# interface_dac_sma_feedback.net
KiCad netlist of a schematic drawn in EAGLE
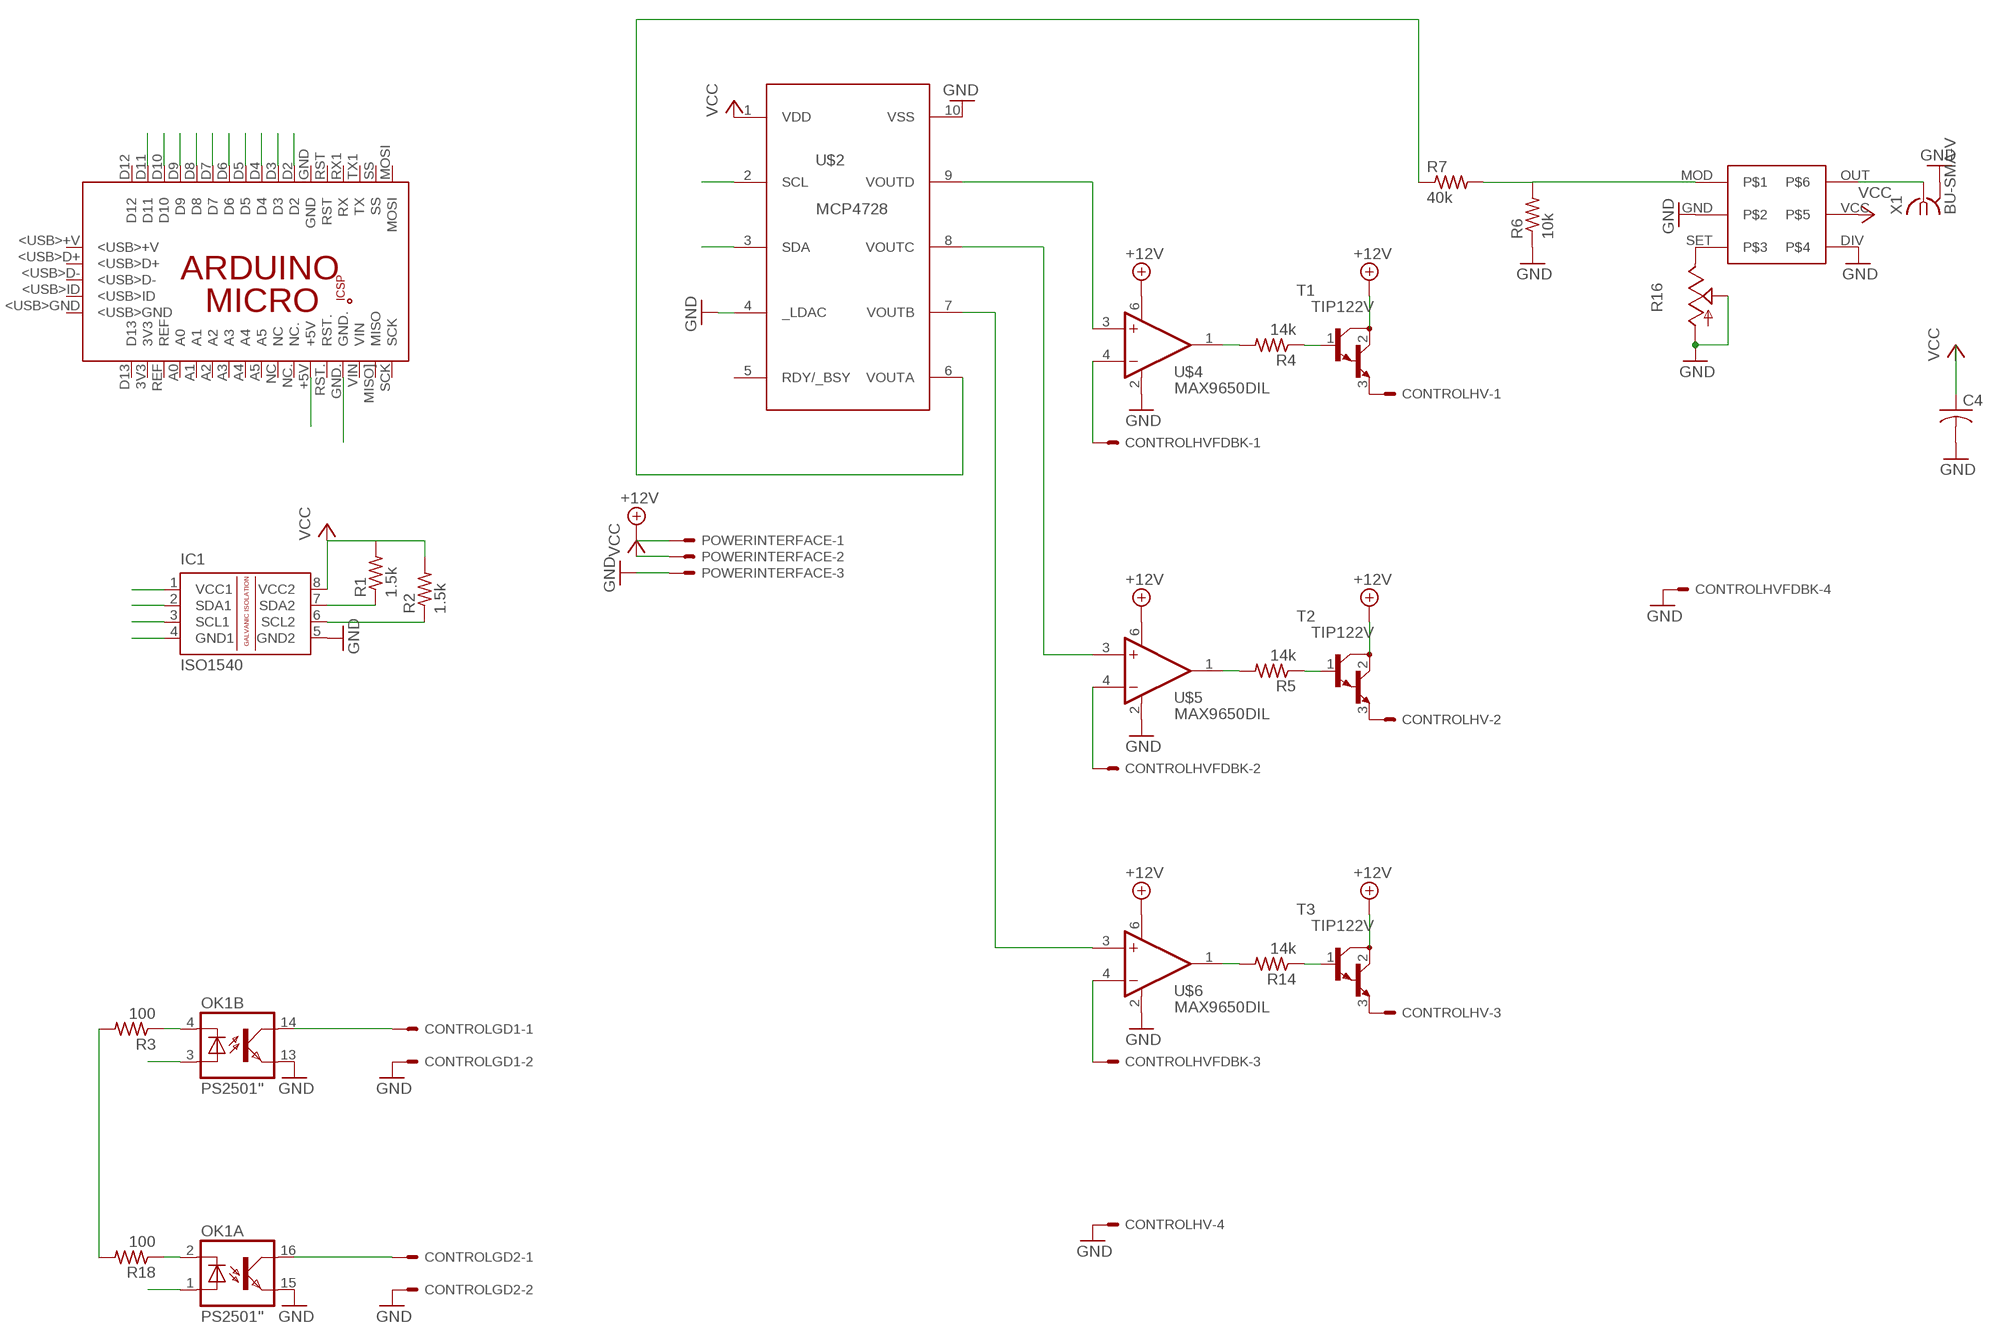
[diagram p0: schematic, sheet 1]

(export (version "E")
  (design (tool "Eeschema 10.0.6"))
  (components
    (comp (ref "C4")
      (value "C-US075-063X106")
      (footprint "eagle-import:C075-063X106")
      (libsource (lib "eagle-import") (part "C-US075-063X106"))
    )
    (comp (ref "CONTROLGD1")
      (value "KK-156-2")
      (footprint "eagle-import:KK-156-2")
      (libsource (lib "eagle-import") (part "KK-156-2"))
    )
    (comp (ref "CONTROLGD2")
      (value "KK-156-2")
      (footprint "eagle-import:KK-156-2")
      (libsource (lib "eagle-import") (part "KK-156-2"))
    )
    (comp (ref "CONTROLHV")
      (value "KK-156-4")
      (footprint "eagle-import:KK-156-4")
      (libsource (lib "eagle-import") (part "KK-156-4"))
    )
    (comp (ref "CONTROLHVFDBK")
      (value "KK-156-4")
      (footprint "eagle-import:KK-156-4")
      (libsource (lib "eagle-import") (part "KK-156-4"))
    )
    (comp (ref "IC1")
      (value "ISO1540")
      (footprint "eagle-import:DIL08")
      (libsource (lib "eagle-import") (part "ISO1540"))
    )
    (comp (ref "OK1")
      (value "PS2501\"")
      (footprint "eagle-import:DIL16")
      (libsource (lib "eagle-import") (part "PS2501{dblquote}"))
    )
    (comp (ref "PCB1")
      (value "ARDUINO_MICRO")
      (footprint "eagle-import:ARDUINO_MICRO")
      (libsource (lib "eagle-import") (part "ARDUINO_MICRO"))
    )
    (comp (ref "POWERINTERFACE")
      (value "KK-156-3")
      (footprint "eagle-import:KK-156-3")
      (libsource (lib "eagle-import") (part "KK-156-3"))
    )
    (comp (ref "R1")
      (value "1.5k")
      (footprint "eagle-import:0207_12")
      (libsource (lib "eagle-import") (part "resistor_R-US_0207/12"))
    )
    (comp (ref "R2")
      (value "1.5k")
      (footprint "eagle-import:0207_12")
      (libsource (lib "eagle-import") (part "resistor_R-US_0207/12"))
    )
    (comp (ref "R3")
      (value "100")
      (footprint "eagle-import:0207_12")
      (libsource (lib "eagle-import") (part "R-US_0207/12"))
    )
    (comp (ref "R4")
      (value "14k")
      (footprint "eagle-import:0207_12")
      (libsource (lib "eagle-import") (part "resistor_R-US_0207/12"))
    )
    (comp (ref "R5")
      (value "14k")
      (footprint "eagle-import:0207_12")
      (libsource (lib "eagle-import") (part "resistor_R-US_0207/12"))
    )
    (comp (ref "R6")
      (value "10k")
      (footprint "eagle-import:0207_12")
      (libsource (lib "eagle-import") (part "resistor_R-US_0207/12"))
    )
    (comp (ref "R7")
      (value "40k")
      (footprint "eagle-import:0207_12")
      (libsource (lib "eagle-import") (part "resistor_R-US_0207/12"))
    )
    (comp (ref "R14")
      (value "14k")
      (footprint "eagle-import:0207_12")
      (libsource (lib "eagle-import") (part "resistor_R-US_0207/12"))
    )
    (comp (ref "R16")
      (value "TRIM_US-B90P")
      (footprint "eagle-import:SP19L")
      (libsource (lib "eagle-import") (part "TRIM_US-B90P"))
    )
    (comp (ref "R18")
      (value "100")
      (footprint "eagle-import:0207_12")
      (libsource (lib "eagle-import") (part "R-US_0207/12"))
    )
    (comp (ref "T1")
      (value "TIP122V")
      (footprint "eagle-import:TO220V")
      (libsource (lib "eagle-import") (part "TIP122V"))
    )
    (comp (ref "T2")
      (value "TIP122V")
      (footprint "eagle-import:TO220V")
      (libsource (lib "eagle-import") (part "TIP122V"))
    )
    (comp (ref "T3")
      (value "TIP122V")
      (footprint "eagle-import:TO220V")
      (libsource (lib "eagle-import") (part "TIP122V"))
    )
    (comp (ref "U$1")
      (value "LTC6992")
      (footprint "eagle-import:DIL06")
      (libsource (lib "eagle-import") (part "LTC6992"))
    )
    (comp (ref "U$2")
      (value "MCP4728DIL")
      (footprint "eagle-import:DIL10")
      (libsource (lib "eagle-import") (part "MCP4728DIL"))
    )
    (comp (ref "U$4")
      (value "MAX9650DIL")
      (footprint "eagle-import:DIL06-4")
      (libsource (lib "eagle-import") (part "MAX9650DIL"))
    )
    (comp (ref "U$5")
      (value "MAX9650DIL")
      (footprint "eagle-import:DIL06-4")
      (libsource (lib "eagle-import") (part "MAX9650DIL"))
    )
    (comp (ref "U$6")
      (value "MAX9650DIL")
      (footprint "eagle-import:DIL06-4")
      (libsource (lib "eagle-import") (part "MAX9650DIL"))
    )
    (comp (ref "X1")
      (value "BU-SMA-V")
      (footprint "eagle-import:BU-SMA-V")
      (libsource (lib "eagle-import") (part "BU-SMA-V"))
    )
  )
  (nets
    (net (code "1") (name "+12V") (class "Default")
      (node (ref "POWERINTERFACE") (pin "1") (pinfunction "S_1") (pintype "passive"))
      (node (ref "T1") (pin "2") (pinfunction "C_2") (pintype "passive"))
      (node (ref "T2") (pin "2") (pinfunction "C_2") (pintype "passive"))
      (node (ref "T3") (pin "2") (pinfunction "C_2") (pintype "passive"))
      (node (ref "U$4") (pin "6") (pinfunction "V+_6") (pintype "power_in"))
      (node (ref "U$5") (pin "6") (pinfunction "V+_6") (pintype "power_in"))
      (node (ref "U$6") (pin "6") (pinfunction "V+_6") (pintype "power_in"))
    )
    (net (code "2") (name "/A+5") (class "Default")
      (node (ref "IC1") (pin "1") (pinfunction "VCC1_1") (pintype "input"))
      (node (ref "PCB1") (pin "+5V") (pinfunction "+5V_+5V") (pintype "bidirectional"))
    )
    (net (code "3") (name "/AGND") (class "Default")
      (node (ref "IC1") (pin "4") (pinfunction "GND1_4") (pintype "input"))
      (node (ref "PCB1") (pin "GND.") (pinfunction "GND._GND.") (pintype "bidirectional"))
      (node (ref "R18") (pin "2") (pinfunction "2_2") (pintype "passive"))
      (node (ref "R3") (pin "2") (pinfunction "2_2") (pintype "passive"))
    )
    (net (code "4") (name "/N$2") (class "Default")
      (node (ref "R6") (pin "2") (pinfunction "2_2") (pintype "passive"))
      (node (ref "R7") (pin "2") (pinfunction "2_2") (pintype "passive"))
      (node (ref "U$1") (pin "MOD") (pinfunction "P$1_MOD") (pintype "bidirectional"))
    )
    (net (code "5") (name "/PWM6") (class "Default")
      (node (ref "OK1") (pin "3") (pinfunction "A_3") (pintype "passive"))
      (node (ref "PCB1") (pin "D6") (pinfunction "D6_D6") (pintype "bidirectional"))
    )
    (net (code "6") (name "/PWM9") (class "Default")
      (node (ref "OK1") (pin "1") (pinfunction "A_1") (pintype "passive"))
      (node (ref "PCB1") (pin "D9") (pinfunction "D9_D9") (pintype "bidirectional"))
    )
    (net (code "7") (name "/SCL") (class "Default")
      (node (ref "IC1") (pin "3") (pinfunction "SCL1_3") (pintype "input"))
      (node (ref "PCB1") (pin "D3") (pinfunction "D3_D3") (pintype "bidirectional"))
    )
    (net (code "8") (name "/SCL_OUT") (class "Default")
      (node (ref "IC1") (pin "6") (pinfunction "SCL2_6") (pintype "input"))
      (node (ref "R2") (pin "1") (pinfunction "1_1") (pintype "passive"))
      (node (ref "U$2") (pin "2") (pinfunction "SCL_2") (pintype "bidirectional"))
    )
    (net (code "9") (name "/SDA") (class "Default")
      (node (ref "IC1") (pin "2") (pinfunction "SDA1_2") (pintype "input"))
      (node (ref "PCB1") (pin "D2") (pinfunction "D2_D2") (pintype "bidirectional"))
    )
    (net (code "10") (name "/SDA_OUT") (class "Default")
      (node (ref "IC1") (pin "7") (pinfunction "SDA2_7") (pintype "input"))
      (node (ref "R1") (pin "1") (pinfunction "1_1") (pintype "passive"))
      (node (ref "U$2") (pin "3") (pinfunction "SDA_3") (pintype "bidirectional"))
    )
    (net (code "11") (name "GND") (class "Default")
      (node (ref "C4") (pin "2") (pinfunction "2_2") (pintype "passive"))
      (node (ref "CONTROLGD1") (pin "2") (pinfunction "S_2") (pintype "passive"))
      (node (ref "CONTROLGD2") (pin "2") (pinfunction "S_2") (pintype "passive"))
      (node (ref "CONTROLHV") (pin "4") (pinfunction "S_4") (pintype "passive"))
      (node (ref "CONTROLHVFDBK") (pin "4") (pinfunction "S_4") (pintype "passive"))
      (node (ref "IC1") (pin "5") (pinfunction "GND2_5") (pintype "input"))
      (node (ref "OK1") (pin "13") (pinfunction "EMI_13") (pintype "passive"))
      (node (ref "OK1") (pin "15") (pinfunction "EMI_15") (pintype "passive"))
      (node (ref "POWERINTERFACE") (pin "3") (pinfunction "S_3") (pintype "passive"))
      (node (ref "R16") (pin "A") (pinfunction "A_A") (pintype "passive"))
      (node (ref "R16") (pin "S") (pinfunction "S_S") (pintype "passive"))
      (node (ref "R6") (pin "1") (pinfunction "1_1") (pintype "passive"))
      (node (ref "U$1") (pin "DIV") (pinfunction "P$4_DIV") (pintype "bidirectional"))
      (node (ref "U$1") (pin "GND") (pinfunction "P$2_GND") (pintype "bidirectional"))
      (node (ref "U$2") (pin "10") (pinfunction "VSS_10") (pintype "bidirectional"))
      (node (ref "U$2") (pin "4") (pinfunction "_LDAC_4") (pintype "bidirectional"))
      (node (ref "U$4") (pin "2") (pinfunction "V-_2") (pintype "power_in"))
      (node (ref "U$5") (pin "2") (pinfunction "V-_2") (pintype "power_in"))
      (node (ref "U$6") (pin "2") (pinfunction "V-_2") (pintype "power_in"))
      (node (ref "X1") (pin "2") (pinfunction "2_2") (pintype "passive"))
      (node (ref "X1") (pin "3") (pinfunction "2_3") (pintype "passive"))
      (node (ref "X1") (pin "4") (pinfunction "2_4") (pintype "passive"))
      (node (ref "X1") (pin "5") (pinfunction "2_5") (pintype "passive"))
    )
    (net (code "12") (name "Net-(CONTROLGD1A-S)") (class "Default")
      (node (ref "CONTROLGD1") (pin "1") (pinfunction "S_1") (pintype "passive"))
      (node (ref "OK1") (pin "14") (pinfunction "COL_14") (pintype "passive"))
    )
    (net (code "13") (name "Net-(CONTROLGD2A-S)") (class "Default")
      (node (ref "CONTROLGD2") (pin "1") (pinfunction "S_1") (pintype "passive"))
      (node (ref "OK1") (pin "16") (pinfunction "COL_16") (pintype "passive"))
    )
    (net (code "14") (name "Net-(CONTROLHVA-S)") (class "Default")
      (node (ref "CONTROLHV") (pin "1") (pinfunction "S_1") (pintype "passive"))
      (node (ref "T1") (pin "3") (pinfunction "E_3") (pintype "passive"))
    )
    (net (code "15") (name "Net-(CONTROLHVB-S)") (class "Default")
      (node (ref "CONTROLHV") (pin "2") (pinfunction "S_2") (pintype "passive"))
      (node (ref "T2") (pin "3") (pinfunction "E_3") (pintype "passive"))
    )
    (net (code "16") (name "Net-(CONTROLHVC-S)") (class "Default")
      (node (ref "CONTROLHV") (pin "3") (pinfunction "S_3") (pintype "passive"))
      (node (ref "T3") (pin "3") (pinfunction "E_3") (pintype "passive"))
    )
    (net (code "17") (name "Net-(CONTROLHVFDBKA-S)") (class "Default")
      (node (ref "CONTROLHVFDBK") (pin "1") (pinfunction "S_1") (pintype "passive"))
      (node (ref "U$4") (pin "4") (pinfunction "-IN_4") (pintype "input"))
    )
    (net (code "18") (name "Net-(CONTROLHVFDBKB-S)") (class "Default")
      (node (ref "CONTROLHVFDBK") (pin "2") (pinfunction "S_2") (pintype "passive"))
      (node (ref "U$5") (pin "4") (pinfunction "-IN_4") (pintype "input"))
    )
    (net (code "19") (name "Net-(CONTROLHVFDBKC-S)") (class "Default")
      (node (ref "CONTROLHVFDBK") (pin "3") (pinfunction "S_3") (pintype "passive"))
      (node (ref "U$6") (pin "4") (pinfunction "-IN_4") (pintype "input"))
    )
    (net (code "20") (name "Net-(OK1A-C)") (class "Default")
      (node (ref "OK1") (pin "2") (pinfunction "C_2") (pintype "passive"))
      (node (ref "R18") (pin "1") (pinfunction "1_1") (pintype "passive"))
    )
    (net (code "21") (name "Net-(OK1B-C)") (class "Default")
      (node (ref "OK1") (pin "4") (pinfunction "C_4") (pintype "passive"))
      (node (ref "R3") (pin "1") (pinfunction "1_1") (pintype "passive"))
    )
    (net (code "22") (name "Net-(T1-B)") (class "Default")
      (node (ref "R4") (pin "1") (pinfunction "1_1") (pintype "passive"))
      (node (ref "T1") (pin "1") (pinfunction "B_1") (pintype "passive"))
    )
    (net (code "23") (name "Net-(T2-B)") (class "Default")
      (node (ref "R5") (pin "1") (pinfunction "1_1") (pintype "passive"))
      (node (ref "T2") (pin "1") (pinfunction "B_1") (pintype "passive"))
    )
    (net (code "24") (name "Net-(T3-B)") (class "Default")
      (node (ref "R14") (pin "1") (pinfunction "1_1") (pintype "passive"))
      (node (ref "T3") (pin "1") (pinfunction "B_1") (pintype "passive"))
    )
    (net (code "25") (name "Net-(U$1-P$3)") (class "Default")
      (node (ref "R16") (pin "E") (pinfunction "E_E") (pintype "passive"))
      (node (ref "U$1") (pin "SET") (pinfunction "P$3_SET") (pintype "bidirectional"))
    )
    (net (code "26") (name "Net-(U$1-P$6)") (class "Default")
      (node (ref "U$1") (pin "OUT") (pinfunction "P$6_OUT") (pintype "bidirectional"))
      (node (ref "X1") (pin "1") (pinfunction "1_1") (pintype "passive"))
    )
    (net (code "27") (name "Net-(U$2-VOUTA)") (class "Default")
      (node (ref "R7") (pin "1") (pinfunction "1_1") (pintype "passive"))
      (node (ref "U$2") (pin "6") (pinfunction "VOUTA_6") (pintype "bidirectional"))
    )
    (net (code "28") (name "Net-(U$2-VOUTB)") (class "Default")
      (node (ref "U$2") (pin "7") (pinfunction "VOUTB_7") (pintype "bidirectional"))
      (node (ref "U$6") (pin "3") (pinfunction "+IN_3") (pintype "input"))
    )
    (net (code "29") (name "Net-(U$2-VOUTC)") (class "Default")
      (node (ref "U$2") (pin "8") (pinfunction "VOUTC_8") (pintype "bidirectional"))
      (node (ref "U$5") (pin "3") (pinfunction "+IN_3") (pintype "input"))
    )
    (net (code "30") (name "Net-(U$2-VOUTD)") (class "Default")
      (node (ref "U$2") (pin "9") (pinfunction "VOUTD_9") (pintype "bidirectional"))
      (node (ref "U$4") (pin "3") (pinfunction "+IN_3") (pintype "input"))
    )
    (net (code "31") (name "Net-(U$4-OUT)") (class "Default")
      (node (ref "R4") (pin "2") (pinfunction "2_2") (pintype "passive"))
      (node (ref "U$4") (pin "1") (pinfunction "OUT_1") (pintype "output"))
    )
    (net (code "32") (name "Net-(U$5-OUT)") (class "Default")
      (node (ref "R5") (pin "2") (pinfunction "2_2") (pintype "passive"))
      (node (ref "U$5") (pin "1") (pinfunction "OUT_1") (pintype "output"))
    )
    (net (code "33") (name "Net-(U$6-OUT)") (class "Default")
      (node (ref "R14") (pin "2") (pinfunction "2_2") (pintype "passive"))
      (node (ref "U$6") (pin "1") (pinfunction "OUT_1") (pintype "output"))
    )
    (net (code "34") (name "VCC") (class "Default")
      (node (ref "C4") (pin "1") (pinfunction "1_1") (pintype "passive"))
      (node (ref "IC1") (pin "8") (pinfunction "VCC2_8") (pintype "input"))
      (node (ref "POWERINTERFACE") (pin "2") (pinfunction "S_2") (pintype "passive"))
      (node (ref "R1") (pin "2") (pinfunction "2_2") (pintype "passive"))
      (node (ref "R2") (pin "2") (pinfunction "2_2") (pintype "passive"))
      (node (ref "U$1") (pin "VCC") (pinfunction "P$5_VCC") (pintype "bidirectional"))
      (node (ref "U$2") (pin "1") (pinfunction "VDD_1") (pintype "bidirectional"))
    )
    (net (code "35") (name "unconnected-(PCB1-MISO-PadMISO])") (class "Default")
      (node (ref "PCB1") (pin "MISO]") (pinfunction "MISO_MISO]") (pintype "bidirectional"))
    )
    (net (code "36") (name "unconnected-(PCB1-Pad3V3)") (class "Default")
      (node (ref "PCB1") (pin "3V3") (pinfunction "3V3_3V3") (pintype "bidirectional"))
    )
    (net (code "37") (name "unconnected-(PCB1-Pad5V)") (class "Default")
      (node (ref "PCB1") (pin "5V") (pinfunction "5V_5V") (pintype "bidirectional"))
    )
    (net (code "38") (name "unconnected-(PCB1-Pad<USB>+V)") (class "Default")
      (node (ref "PCB1") (pin "<USB>+V") (pinfunction "<USB>+V_<USB>+V") (pintype "bidirectional"))
    )
    (net (code "39") (name "unconnected-(PCB1-Pad<USB>D+)") (class "Default")
      (node (ref "PCB1") (pin "<USB>D+") (pinfunction "<USB>D+_<USB>D+") (pintype "bidirectional"))
    )
    (net (code "40") (name "unconnected-(PCB1-Pad<USB>D-)") (class "Default")
      (node (ref "PCB1") (pin "<USB>D-") (pinfunction "<USB>D-_<USB>D-") (pintype "bidirectional"))
    )
    (net (code "41") (name "unconnected-(PCB1-Pad<USB>GND)") (class "Default")
      (node (ref "PCB1") (pin "<USB>GND") (pinfunction "<USB>GND_<USB>GND") (pintype "bidirectional"))
    )
    (net (code "42") (name "unconnected-(PCB1-Pad<USB>ID)") (class "Default")
      (node (ref "PCB1") (pin "<USB>ID") (pinfunction "<USB>ID_<USB>ID") (pintype "bidirectional"))
    )
    (net (code "43") (name "unconnected-(PCB1-PadA0)") (class "Default")
      (node (ref "PCB1") (pin "A0") (pinfunction "A0_A0") (pintype "bidirectional"))
    )
    (net (code "44") (name "unconnected-(PCB1-PadA1)") (class "Default")
      (node (ref "PCB1") (pin "A1") (pinfunction "A1_A1") (pintype "bidirectional"))
    )
    (net (code "45") (name "unconnected-(PCB1-PadA2)") (class "Default")
      (node (ref "PCB1") (pin "A2") (pinfunction "A2_A2") (pintype "bidirectional"))
    )
    (net (code "46") (name "unconnected-(PCB1-PadA3)") (class "Default")
      (node (ref "PCB1") (pin "A3") (pinfunction "A3_A3") (pintype "bidirectional"))
    )
    (net (code "47") (name "unconnected-(PCB1-PadA4)") (class "Default")
      (node (ref "PCB1") (pin "A4") (pinfunction "A4_A4") (pintype "bidirectional"))
    )
    (net (code "48") (name "unconnected-(PCB1-PadA5)") (class "Default")
      (node (ref "PCB1") (pin "A5") (pinfunction "A5_A5") (pintype "bidirectional"))
    )
    (net (code "49") (name "unconnected-(PCB1-PadD4)") (class "Default")
      (node (ref "PCB1") (pin "D4") (pinfunction "D4_D4") (pintype "bidirectional"))
    )
    (net (code "50") (name "unconnected-(PCB1-PadD5)") (class "Default")
      (node (ref "PCB1") (pin "D5") (pinfunction "D5_D5") (pintype "bidirectional"))
    )
    (net (code "51") (name "unconnected-(PCB1-PadD7)") (class "Default")
      (node (ref "PCB1") (pin "D7") (pinfunction "D7_D7") (pintype "bidirectional"))
    )
    (net (code "52") (name "unconnected-(PCB1-PadD8)") (class "Default")
      (node (ref "PCB1") (pin "D8") (pinfunction "D8_D8") (pintype "bidirectional"))
    )
    (net (code "53") (name "unconnected-(PCB1-PadD10)") (class "Default")
      (node (ref "PCB1") (pin "D10") (pinfunction "D10_D10") (pintype "bidirectional"))
    )
    (net (code "54") (name "unconnected-(PCB1-PadD11)") (class "Default")
      (node (ref "PCB1") (pin "D11") (pinfunction "D11_D11") (pintype "bidirectional"))
    )
    (net (code "55") (name "unconnected-(PCB1-PadD12)") (class "Default")
      (node (ref "PCB1") (pin "D12") (pinfunction "D12_D12") (pintype "bidirectional"))
    )
    (net (code "56") (name "unconnected-(PCB1-PadD13)") (class "Default")
      (node (ref "PCB1") (pin "D13") (pinfunction "D13_D13") (pintype "bidirectional"))
    )
    (net (code "57") (name "unconnected-(PCB1-PadGND)") (class "Default")
      (node (ref "PCB1") (pin "GND") (pinfunction "GND_GND") (pintype "bidirectional"))
    )
    (net (code "58") (name "unconnected-(PCB1-PadGND_)") (class "Default")
      (node (ref "PCB1") (pin "GND_") (pinfunction "GND__GND_") (pintype "bidirectional"))
    )
    (net (code "59") (name "unconnected-(PCB1-PadMISO.)") (class "Default")
      (node (ref "PCB1") (pin "MISO.") (pinfunction "MISO._MISO.") (pintype "bidirectional"))
    )
    (net (code "60") (name "unconnected-(PCB1-PadMOSI)") (class "Default")
      (node (ref "PCB1") (pin "MOSI") (pinfunction "MOSI_MOSI") (pintype "bidirectional"))
    )
    (net (code "61") (name "unconnected-(PCB1-PadMOSI.)") (class "Default")
      (node (ref "PCB1") (pin "MOSI.") (pinfunction "MOSI._MOSI.") (pintype "bidirectional"))
    )
    (net (code "62") (name "unconnected-(PCB1-PadNC)") (class "Default")
      (node (ref "PCB1") (pin "NC") (pinfunction "NC_NC") (pintype "bidirectional"))
    )
    (net (code "63") (name "unconnected-(PCB1-PadNC.)") (class "Default")
      (node (ref "PCB1") (pin "NC.") (pinfunction "NC._NC.") (pintype "bidirectional"))
    )
    (net (code "64") (name "unconnected-(PCB1-PadREF)") (class "Default")
      (node (ref "PCB1") (pin "REF") (pinfunction "REF_REF") (pintype "bidirectional"))
    )
    (net (code "65") (name "unconnected-(PCB1-PadRESET..)") (class "Default")
      (node (ref "PCB1") (pin "RESET..") (pinfunction "RESET.._RESET..") (pintype "bidirectional"))
    )
    (net (code "66") (name "unconnected-(PCB1-PadRST)") (class "Default")
      (node (ref "PCB1") (pin "RST") (pinfunction "RST_RST") (pintype "bidirectional"))
    )
    (net (code "67") (name "unconnected-(PCB1-PadRST.)") (class "Default")
      (node (ref "PCB1") (pin "RST.") (pinfunction "RST._RST.") (pintype "bidirectional"))
    )
    (net (code "68") (name "unconnected-(PCB1-PadSCK)") (class "Default")
      (node (ref "PCB1") (pin "SCK") (pinfunction "SCK_SCK") (pintype "bidirectional"))
    )
    (net (code "69") (name "unconnected-(PCB1-PadSCK.)") (class "Default")
      (node (ref "PCB1") (pin "SCK.") (pinfunction "SCK._SCK.") (pintype "bidirectional"))
    )
    (net (code "70") (name "unconnected-(PCB1-PadSS)") (class "Default")
      (node (ref "PCB1") (pin "SS") (pinfunction "SS_SS") (pintype "bidirectional"))
    )
    (net (code "71") (name "unconnected-(PCB1-PadVIN)") (class "Default")
      (node (ref "PCB1") (pin "VIN") (pinfunction "VIN_VIN") (pintype "bidirectional"))
    )
    (net (code "72") (name "unconnected-(PCB1-RX-PadRX1)") (class "Default")
      (node (ref "PCB1") (pin "RX1") (pinfunction "RX_RX1") (pintype "bidirectional"))
    )
    (net (code "73") (name "unconnected-(PCB1-TX-PadTX1)") (class "Default")
      (node (ref "PCB1") (pin "TX1") (pinfunction "TX_TX1") (pintype "bidirectional"))
    )
    (net (code "74") (name "unconnected-(U$2-RDY{slash}_BSY-Pad5)") (class "Default")
      (node (ref "U$2") (pin "5") (pinfunction "RDY/_BSY_5") (pintype "bidirectional"))
    )
  )
)
